# 05-ORStatusLed.net
KiCad netlist of a schematic drawn in Altium Designer
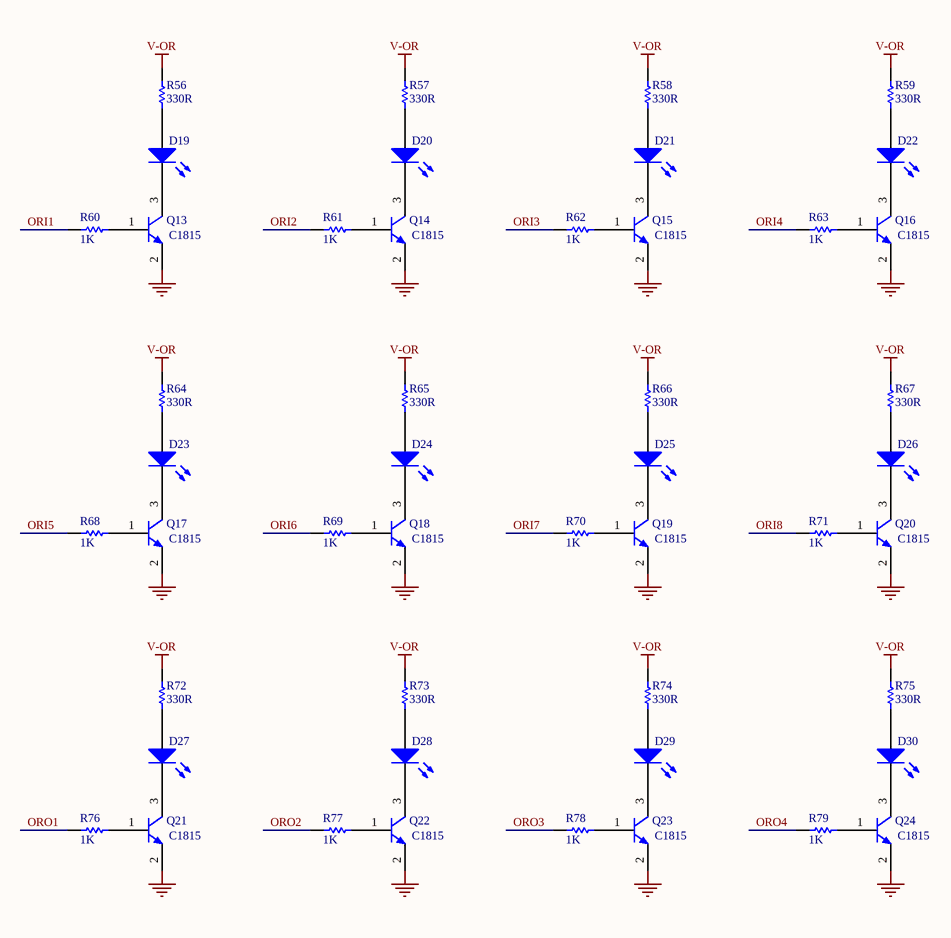
[diagram p0: 05-ORStatusLed.SchDoc]

(export (version "E")
  (design (tool "Eeschema 10.0.6"))
  (components
    (comp (ref "D19")
      (value "LED")
      (footprint "LED-3528")
      (description "Typical RED, GREEN, YELLOW, AMBER GaAs LED")
      (fields (field (name "PUBLISHER") "Altium Limited"))
      (libsource (lib "Miscellaneous Devices") (part "LED2"))
    )
    (comp (ref "D20")
      (value "LED")
      (footprint "LED-3528")
      (description "Typical RED, GREEN, YELLOW, AMBER GaAs LED")
      (fields (field (name "PUBLISHER") "Altium Limited"))
      (libsource (lib "Miscellaneous Devices") (part "LED2"))
    )
    (comp (ref "D21")
      (value "LED")
      (footprint "LED-3528")
      (description "Typical RED, GREEN, YELLOW, AMBER GaAs LED")
      (fields (field (name "PUBLISHER") "Altium Limited"))
      (libsource (lib "Miscellaneous Devices") (part "LED2"))
    )
    (comp (ref "D22")
      (value "LED")
      (footprint "LED-3528")
      (description "Typical RED, GREEN, YELLOW, AMBER GaAs LED")
      (fields (field (name "PUBLISHER") "Altium Limited"))
      (libsource (lib "Miscellaneous Devices") (part "LED2"))
    )
    (comp (ref "D23")
      (value "LED")
      (footprint "LED-3528")
      (description "Typical RED, GREEN, YELLOW, AMBER GaAs LED")
      (fields (field (name "PUBLISHER") "Altium Limited"))
      (libsource (lib "Miscellaneous Devices") (part "LED2"))
    )
    (comp (ref "D24")
      (value "LED")
      (footprint "LED-3528")
      (description "Typical RED, GREEN, YELLOW, AMBER GaAs LED")
      (fields (field (name "PUBLISHER") "Altium Limited"))
      (libsource (lib "Miscellaneous Devices") (part "LED2"))
    )
    (comp (ref "D25")
      (value "LED")
      (footprint "LED-3528")
      (description "Typical RED, GREEN, YELLOW, AMBER GaAs LED")
      (fields (field (name "PUBLISHER") "Altium Limited"))
      (libsource (lib "Miscellaneous Devices") (part "LED2"))
    )
    (comp (ref "D26")
      (value "LED")
      (footprint "LED-3528")
      (description "Typical RED, GREEN, YELLOW, AMBER GaAs LED")
      (fields (field (name "PUBLISHER") "Altium Limited"))
      (libsource (lib "Miscellaneous Devices") (part "LED2"))
    )
    (comp (ref "D27")
      (value "LED")
      (footprint "LED-3528")
      (description "Typical RED, GREEN, YELLOW, AMBER GaAs LED")
      (fields (field (name "PUBLISHER") "Altium Limited"))
      (libsource (lib "Miscellaneous Devices") (part "LED2"))
    )
    (comp (ref "D28")
      (value "LED")
      (footprint "LED-3528")
      (description "Typical RED, GREEN, YELLOW, AMBER GaAs LED")
      (fields (field (name "PUBLISHER") "Altium Limited"))
      (libsource (lib "Miscellaneous Devices") (part "LED2"))
    )
    (comp (ref "D29")
      (value "LED")
      (footprint "LED-3528")
      (description "Typical RED, GREEN, YELLOW, AMBER GaAs LED")
      (fields (field (name "PUBLISHER") "Altium Limited"))
      (libsource (lib "Miscellaneous Devices") (part "LED2"))
    )
    (comp (ref "D30")
      (value "LED")
      (footprint "LED-3528")
      (description "Typical RED, GREEN, YELLOW, AMBER GaAs LED")
      (fields (field (name "PUBLISHER") "Altium Limited"))
      (libsource (lib "Miscellaneous Devices") (part "LED2"))
    )
    (comp (ref "Q13")
      (value "C1815")
      (footprint "SOT23-321")
      (description "NPN Bipolar Transistor")
      (fields (field (name "Comment") "C1815-SMD"))
      (libsource (lib "Miscellaneous Devices") (part "NPN"))
    )
    (comp (ref "Q14")
      (value "C1815")
      (footprint "SOT23-321")
      (description "NPN Bipolar Transistor")
      (fields (field (name "Comment") "C1815-SMD"))
      (libsource (lib "Miscellaneous Devices") (part "NPN"))
    )
    (comp (ref "Q15")
      (value "C1815")
      (footprint "SOT23-321")
      (description "NPN Bipolar Transistor")
      (fields (field (name "Comment") "C1815-SMD"))
      (libsource (lib "Miscellaneous Devices") (part "NPN"))
    )
    (comp (ref "Q16")
      (value "C1815")
      (footprint "SOT23-321")
      (description "NPN Bipolar Transistor")
      (fields (field (name "Comment") "C1815-SMD"))
      (libsource (lib "Miscellaneous Devices") (part "NPN"))
    )
    (comp (ref "Q17")
      (value "C1815")
      (footprint "SOT23-321")
      (description "NPN Bipolar Transistor")
      (fields (field (name "Comment") "C1815-SMD"))
      (libsource (lib "Miscellaneous Devices") (part "NPN"))
    )
    (comp (ref "Q18")
      (value "C1815")
      (footprint "SOT23-321")
      (description "NPN Bipolar Transistor")
      (fields (field (name "Comment") "C1815-SMD"))
      (libsource (lib "Miscellaneous Devices") (part "NPN"))
    )
    (comp (ref "Q19")
      (value "C1815")
      (footprint "SOT23-321")
      (description "NPN Bipolar Transistor")
      (fields (field (name "Comment") "C1815-SMD"))
      (libsource (lib "Miscellaneous Devices") (part "NPN"))
    )
    (comp (ref "Q20")
      (value "C1815")
      (footprint "SOT23-321")
      (description "NPN Bipolar Transistor")
      (fields (field (name "Comment") "C1815-SMD"))
      (libsource (lib "Miscellaneous Devices") (part "NPN"))
    )
    (comp (ref "Q21")
      (value "C1815")
      (footprint "SOT23-321")
      (description "NPN Bipolar Transistor")
      (fields (field (name "Comment") "C1815-SMD"))
      (libsource (lib "Miscellaneous Devices") (part "NPN"))
    )
    (comp (ref "Q22")
      (value "C1815")
      (footprint "SOT23-321")
      (description "NPN Bipolar Transistor")
      (fields (field (name "Comment") "C1815-SMD"))
      (libsource (lib "Miscellaneous Devices") (part "NPN"))
    )
    (comp (ref "Q23")
      (value "C1815")
      (footprint "SOT23-321")
      (description "NPN Bipolar Transistor")
      (fields (field (name "Comment") "C1815-SMD"))
      (libsource (lib "Miscellaneous Devices") (part "NPN"))
    )
    (comp (ref "Q24")
      (value "C1815")
      (footprint "SOT23-321")
      (description "NPN Bipolar Transistor")
      (fields (field (name "Comment") "C1815-SMD"))
      (libsource (lib "Miscellaneous Devices") (part "NPN"))
    )
    (comp (ref "R56")
      (value "330R")
      (footprint "R-0805")
      (description "Resistor")
      (fields (field (name "PUBLISHER") "Altium Limited"))
      (libsource (lib "Miscellaneous Devices") (part "Res1"))
    )
    (comp (ref "R57")
      (value "330R")
      (footprint "R-0805")
      (description "Resistor")
      (fields (field (name "PUBLISHER") "Altium Limited"))
      (libsource (lib "Miscellaneous Devices") (part "Res1"))
    )
    (comp (ref "R58")
      (value "330R")
      (footprint "R-0805")
      (description "Resistor")
      (fields (field (name "PUBLISHER") "Altium Limited"))
      (libsource (lib "Miscellaneous Devices") (part "Res1"))
    )
    (comp (ref "R59")
      (value "330R")
      (footprint "R-0805")
      (description "Resistor")
      (fields (field (name "PUBLISHER") "Altium Limited"))
      (libsource (lib "Miscellaneous Devices") (part "Res1"))
    )
    (comp (ref "R60")
      (value "1K")
      (footprint "R-0805")
      (description "Resistor")
      (fields (field (name "PUBLISHER") "Altium Limited"))
      (libsource (lib "Miscellaneous Devices") (part "Res1"))
    )
    (comp (ref "R61")
      (value "1K")
      (footprint "R-0805")
      (description "Resistor")
      (fields (field (name "PUBLISHER") "Altium Limited"))
      (libsource (lib "Miscellaneous Devices") (part "Res1"))
    )
    (comp (ref "R62")
      (value "1K")
      (footprint "R-0805")
      (description "Resistor")
      (fields (field (name "PUBLISHER") "Altium Limited"))
      (libsource (lib "Miscellaneous Devices") (part "Res1"))
    )
    (comp (ref "R63")
      (value "1K")
      (footprint "R-0805")
      (description "Resistor")
      (fields (field (name "PUBLISHER") "Altium Limited"))
      (libsource (lib "Miscellaneous Devices") (part "Res1"))
    )
    (comp (ref "R64")
      (value "330R")
      (footprint "R-0805")
      (description "Resistor")
      (fields (field (name "PUBLISHER") "Altium Limited"))
      (libsource (lib "Miscellaneous Devices") (part "Res1"))
    )
    (comp (ref "R65")
      (value "330R")
      (footprint "R-0805")
      (description "Resistor")
      (fields (field (name "PUBLISHER") "Altium Limited"))
      (libsource (lib "Miscellaneous Devices") (part "Res1"))
    )
    (comp (ref "R66")
      (value "330R")
      (footprint "R-0805")
      (description "Resistor")
      (fields (field (name "PUBLISHER") "Altium Limited"))
      (libsource (lib "Miscellaneous Devices") (part "Res1"))
    )
    (comp (ref "R67")
      (value "330R")
      (footprint "R-0805")
      (description "Resistor")
      (fields (field (name "PUBLISHER") "Altium Limited"))
      (libsource (lib "Miscellaneous Devices") (part "Res1"))
    )
    (comp (ref "R68")
      (value "1K")
      (footprint "R-0805")
      (description "Resistor")
      (fields (field (name "PUBLISHER") "Altium Limited"))
      (libsource (lib "Miscellaneous Devices") (part "Res1"))
    )
    (comp (ref "R69")
      (value "1K")
      (footprint "R-0805")
      (description "Resistor")
      (fields (field (name "PUBLISHER") "Altium Limited"))
      (libsource (lib "Miscellaneous Devices") (part "Res1"))
    )
    (comp (ref "R70")
      (value "1K")
      (footprint "R-0805")
      (description "Resistor")
      (fields (field (name "PUBLISHER") "Altium Limited"))
      (libsource (lib "Miscellaneous Devices") (part "Res1"))
    )
    (comp (ref "R71")
      (value "1K")
      (footprint "R-0805")
      (description "Resistor")
      (fields (field (name "PUBLISHER") "Altium Limited"))
      (libsource (lib "Miscellaneous Devices") (part "Res1"))
    )
    (comp (ref "R72")
      (value "330R")
      (footprint "R-0805")
      (description "Resistor")
      (fields (field (name "PUBLISHER") "Altium Limited"))
      (libsource (lib "Miscellaneous Devices") (part "Res1"))
    )
    (comp (ref "R73")
      (value "330R")
      (footprint "R-0805")
      (description "Resistor")
      (fields (field (name "PUBLISHER") "Altium Limited"))
      (libsource (lib "Miscellaneous Devices") (part "Res1"))
    )
    (comp (ref "R74")
      (value "330R")
      (footprint "R-0805")
      (description "Resistor")
      (fields (field (name "PUBLISHER") "Altium Limited"))
      (libsource (lib "Miscellaneous Devices") (part "Res1"))
    )
    (comp (ref "R75")
      (value "330R")
      (footprint "R-0805")
      (description "Resistor")
      (fields (field (name "PUBLISHER") "Altium Limited"))
      (libsource (lib "Miscellaneous Devices") (part "Res1"))
    )
    (comp (ref "R76")
      (value "1K")
      (footprint "R-0805")
      (description "Resistor")
      (fields (field (name "PUBLISHER") "Altium Limited"))
      (libsource (lib "Miscellaneous Devices") (part "Res1"))
    )
    (comp (ref "R77")
      (value "1K")
      (footprint "R-0805")
      (description "Resistor")
      (fields (field (name "PUBLISHER") "Altium Limited"))
      (libsource (lib "Miscellaneous Devices") (part "Res1"))
    )
    (comp (ref "R78")
      (value "1K")
      (footprint "R-0805")
      (description "Resistor")
      (fields (field (name "PUBLISHER") "Altium Limited"))
      (libsource (lib "Miscellaneous Devices") (part "Res1"))
    )
    (comp (ref "R79")
      (value "1K")
      (footprint "R-0805")
      (description "Resistor")
      (fields (field (name "PUBLISHER") "Altium Limited"))
      (libsource (lib "Miscellaneous Devices") (part "Res1"))
    )
  )
  (nets
    (net (code "1") (name "/ORI1") (class "Default")
      (node (ref "R60") (pin "2") (pinfunction "2_2") (pintype "passive"))
    )
    (net (code "2") (name "/ORI2") (class "Default")
      (node (ref "R61") (pin "2") (pinfunction "2_2") (pintype "passive"))
    )
    (net (code "3") (name "/ORI3") (class "Default")
      (node (ref "R62") (pin "2") (pinfunction "2_2") (pintype "passive"))
    )
    (net (code "4") (name "/ORI4") (class "Default")
      (node (ref "R63") (pin "2") (pinfunction "2_2") (pintype "passive"))
    )
    (net (code "5") (name "/ORI5") (class "Default")
      (node (ref "R68") (pin "2") (pinfunction "2_2") (pintype "passive"))
    )
    (net (code "6") (name "/ORI6") (class "Default")
      (node (ref "R69") (pin "2") (pinfunction "2_2") (pintype "passive"))
    )
    (net (code "7") (name "/ORI7") (class "Default")
      (node (ref "R70") (pin "2") (pinfunction "2_2") (pintype "passive"))
    )
    (net (code "8") (name "/ORI8") (class "Default")
      (node (ref "R71") (pin "2") (pinfunction "2_2") (pintype "passive"))
    )
    (net (code "9") (name "/ORO1") (class "Default")
      (node (ref "R76") (pin "2") (pinfunction "2_2") (pintype "passive"))
    )
    (net (code "10") (name "/ORO2") (class "Default")
      (node (ref "R77") (pin "2") (pinfunction "2_2") (pintype "passive"))
    )
    (net (code "11") (name "/ORO3") (class "Default")
      (node (ref "R78") (pin "2") (pinfunction "2_2") (pintype "passive"))
    )
    (net (code "12") (name "/ORO4") (class "Default")
      (node (ref "R79") (pin "2") (pinfunction "2_2") (pintype "passive"))
    )
    (net (code "13") (name "GND") (class "Default")
      (node (ref "Q13") (pin "2") (pinfunction "E_2") (pintype "passive"))
      (node (ref "Q14") (pin "2") (pinfunction "E_2") (pintype "passive"))
      (node (ref "Q15") (pin "2") (pinfunction "E_2") (pintype "passive"))
      (node (ref "Q16") (pin "2") (pinfunction "E_2") (pintype "passive"))
      (node (ref "Q17") (pin "2") (pinfunction "E_2") (pintype "passive"))
      (node (ref "Q18") (pin "2") (pinfunction "E_2") (pintype "passive"))
      (node (ref "Q19") (pin "2") (pinfunction "E_2") (pintype "passive"))
      (node (ref "Q20") (pin "2") (pinfunction "E_2") (pintype "passive"))
      (node (ref "Q21") (pin "2") (pinfunction "E_2") (pintype "passive"))
      (node (ref "Q22") (pin "2") (pinfunction "E_2") (pintype "passive"))
      (node (ref "Q23") (pin "2") (pinfunction "E_2") (pintype "passive"))
      (node (ref "Q24") (pin "2") (pinfunction "E_2") (pintype "passive"))
    )
    (net (code "14") (name "Net-(D19-A)") (class "Default")
      (node (ref "D19") (pin "1") (pinfunction "A_1") (pintype "passive"))
      (node (ref "R56") (pin "1") (pinfunction "1_1") (pintype "passive"))
    )
    (net (code "15") (name "Net-(D19-K)") (class "Default")
      (node (ref "D19") (pin "2") (pinfunction "K_2") (pintype "passive"))
      (node (ref "Q13") (pin "3") (pinfunction "C_3") (pintype "passive"))
    )
    (net (code "16") (name "Net-(D20-A)") (class "Default")
      (node (ref "D20") (pin "1") (pinfunction "A_1") (pintype "passive"))
      (node (ref "R57") (pin "1") (pinfunction "1_1") (pintype "passive"))
    )
    (net (code "17") (name "Net-(D20-K)") (class "Default")
      (node (ref "D20") (pin "2") (pinfunction "K_2") (pintype "passive"))
      (node (ref "Q14") (pin "3") (pinfunction "C_3") (pintype "passive"))
    )
    (net (code "18") (name "Net-(D21-A)") (class "Default")
      (node (ref "D21") (pin "1") (pinfunction "A_1") (pintype "passive"))
      (node (ref "R58") (pin "1") (pinfunction "1_1") (pintype "passive"))
    )
    (net (code "19") (name "Net-(D21-K)") (class "Default")
      (node (ref "D21") (pin "2") (pinfunction "K_2") (pintype "passive"))
      (node (ref "Q15") (pin "3") (pinfunction "C_3") (pintype "passive"))
    )
    (net (code "20") (name "Net-(D22-A)") (class "Default")
      (node (ref "D22") (pin "1") (pinfunction "A_1") (pintype "passive"))
      (node (ref "R59") (pin "1") (pinfunction "1_1") (pintype "passive"))
    )
    (net (code "21") (name "Net-(D22-K)") (class "Default")
      (node (ref "D22") (pin "2") (pinfunction "K_2") (pintype "passive"))
      (node (ref "Q16") (pin "3") (pinfunction "C_3") (pintype "passive"))
    )
    (net (code "22") (name "Net-(D23-A)") (class "Default")
      (node (ref "D23") (pin "1") (pinfunction "A_1") (pintype "passive"))
      (node (ref "R64") (pin "1") (pinfunction "1_1") (pintype "passive"))
    )
    (net (code "23") (name "Net-(D23-K)") (class "Default")
      (node (ref "D23") (pin "2") (pinfunction "K_2") (pintype "passive"))
      (node (ref "Q17") (pin "3") (pinfunction "C_3") (pintype "passive"))
    )
    (net (code "24") (name "Net-(D24-A)") (class "Default")
      (node (ref "D24") (pin "1") (pinfunction "A_1") (pintype "passive"))
      (node (ref "R65") (pin "1") (pinfunction "1_1") (pintype "passive"))
    )
    (net (code "25") (name "Net-(D24-K)") (class "Default")
      (node (ref "D24") (pin "2") (pinfunction "K_2") (pintype "passive"))
      (node (ref "Q18") (pin "3") (pinfunction "C_3") (pintype "passive"))
    )
    (net (code "26") (name "Net-(D25-A)") (class "Default")
      (node (ref "D25") (pin "1") (pinfunction "A_1") (pintype "passive"))
      (node (ref "R66") (pin "1") (pinfunction "1_1") (pintype "passive"))
    )
    (net (code "27") (name "Net-(D25-K)") (class "Default")
      (node (ref "D25") (pin "2") (pinfunction "K_2") (pintype "passive"))
      (node (ref "Q19") (pin "3") (pinfunction "C_3") (pintype "passive"))
    )
    (net (code "28") (name "Net-(D26-A)") (class "Default")
      (node (ref "D26") (pin "1") (pinfunction "A_1") (pintype "passive"))
      (node (ref "R67") (pin "1") (pinfunction "1_1") (pintype "passive"))
    )
    (net (code "29") (name "Net-(D26-K)") (class "Default")
      (node (ref "D26") (pin "2") (pinfunction "K_2") (pintype "passive"))
      (node (ref "Q20") (pin "3") (pinfunction "C_3") (pintype "passive"))
    )
    (net (code "30") (name "Net-(D27-A)") (class "Default")
      (node (ref "D27") (pin "1") (pinfunction "A_1") (pintype "passive"))
      (node (ref "R72") (pin "1") (pinfunction "1_1") (pintype "passive"))
    )
    (net (code "31") (name "Net-(D27-K)") (class "Default")
      (node (ref "D27") (pin "2") (pinfunction "K_2") (pintype "passive"))
      (node (ref "Q21") (pin "3") (pinfunction "C_3") (pintype "passive"))
    )
    (net (code "32") (name "Net-(D28-A)") (class "Default")
      (node (ref "D28") (pin "1") (pinfunction "A_1") (pintype "passive"))
      (node (ref "R73") (pin "1") (pinfunction "1_1") (pintype "passive"))
    )
    (net (code "33") (name "Net-(D28-K)") (class "Default")
      (node (ref "D28") (pin "2") (pinfunction "K_2") (pintype "passive"))
      (node (ref "Q22") (pin "3") (pinfunction "C_3") (pintype "passive"))
    )
    (net (code "34") (name "Net-(D29-A)") (class "Default")
      (node (ref "D29") (pin "1") (pinfunction "A_1") (pintype "passive"))
      (node (ref "R74") (pin "1") (pinfunction "1_1") (pintype "passive"))
    )
    (net (code "35") (name "Net-(D29-K)") (class "Default")
      (node (ref "D29") (pin "2") (pinfunction "K_2") (pintype "passive"))
      (node (ref "Q23") (pin "3") (pinfunction "C_3") (pintype "passive"))
    )
    (net (code "36") (name "Net-(D30-A)") (class "Default")
      (node (ref "D30") (pin "1") (pinfunction "A_1") (pintype "passive"))
      (node (ref "R75") (pin "1") (pinfunction "1_1") (pintype "passive"))
    )
    (net (code "37") (name "Net-(D30-K)") (class "Default")
      (node (ref "D30") (pin "2") (pinfunction "K_2") (pintype "passive"))
      (node (ref "Q24") (pin "3") (pinfunction "C_3") (pintype "passive"))
    )
    (net (code "38") (name "Net-(Q13-B)") (class "Default")
      (node (ref "Q13") (pin "1") (pinfunction "B_1") (pintype "passive"))
      (node (ref "R60") (pin "1") (pinfunction "1_1") (pintype "passive"))
    )
    (net (code "39") (name "Net-(Q14-B)") (class "Default")
      (node (ref "Q14") (pin "1") (pinfunction "B_1") (pintype "passive"))
      (node (ref "R61") (pin "1") (pinfunction "1_1") (pintype "passive"))
    )
    (net (code "40") (name "Net-(Q15-B)") (class "Default")
      (node (ref "Q15") (pin "1") (pinfunction "B_1") (pintype "passive"))
      (node (ref "R62") (pin "1") (pinfunction "1_1") (pintype "passive"))
    )
    (net (code "41") (name "Net-(Q16-B)") (class "Default")
      (node (ref "Q16") (pin "1") (pinfunction "B_1") (pintype "passive"))
      (node (ref "R63") (pin "1") (pinfunction "1_1") (pintype "passive"))
    )
    (net (code "42") (name "Net-(Q17-B)") (class "Default")
      (node (ref "Q17") (pin "1") (pinfunction "B_1") (pintype "passive"))
      (node (ref "R68") (pin "1") (pinfunction "1_1") (pintype "passive"))
    )
    (net (code "43") (name "Net-(Q18-B)") (class "Default")
      (node (ref "Q18") (pin "1") (pinfunction "B_1") (pintype "passive"))
      (node (ref "R69") (pin "1") (pinfunction "1_1") (pintype "passive"))
    )
    (net (code "44") (name "Net-(Q19-B)") (class "Default")
      (node (ref "Q19") (pin "1") (pinfunction "B_1") (pintype "passive"))
      (node (ref "R70") (pin "1") (pinfunction "1_1") (pintype "passive"))
    )
    (net (code "45") (name "Net-(Q20-B)") (class "Default")
      (node (ref "Q20") (pin "1") (pinfunction "B_1") (pintype "passive"))
      (node (ref "R71") (pin "1") (pinfunction "1_1") (pintype "passive"))
    )
    (net (code "46") (name "Net-(Q21-B)") (class "Default")
      (node (ref "Q21") (pin "1") (pinfunction "B_1") (pintype "passive"))
      (node (ref "R76") (pin "1") (pinfunction "1_1") (pintype "passive"))
    )
    (net (code "47") (name "Net-(Q22-B)") (class "Default")
      (node (ref "Q22") (pin "1") (pinfunction "B_1") (pintype "passive"))
      (node (ref "R77") (pin "1") (pinfunction "1_1") (pintype "passive"))
    )
    (net (code "48") (name "Net-(Q23-B)") (class "Default")
      (node (ref "Q23") (pin "1") (pinfunction "B_1") (pintype "passive"))
      (node (ref "R78") (pin "1") (pinfunction "1_1") (pintype "passive"))
    )
    (net (code "49") (name "Net-(Q24-B)") (class "Default")
      (node (ref "Q24") (pin "1") (pinfunction "B_1") (pintype "passive"))
      (node (ref "R79") (pin "1") (pinfunction "1_1") (pintype "passive"))
    )
    (net (code "50") (name "V-OR") (class "Default")
      (node (ref "R56") (pin "2") (pinfunction "2_2") (pintype "passive"))
      (node (ref "R57") (pin "2") (pinfunction "2_2") (pintype "passive"))
      (node (ref "R58") (pin "2") (pinfunction "2_2") (pintype "passive"))
      (node (ref "R59") (pin "2") (pinfunction "2_2") (pintype "passive"))
      (node (ref "R64") (pin "2") (pinfunction "2_2") (pintype "passive"))
      (node (ref "R65") (pin "2") (pinfunction "2_2") (pintype "passive"))
      (node (ref "R66") (pin "2") (pinfunction "2_2") (pintype "passive"))
      (node (ref "R67") (pin "2") (pinfunction "2_2") (pintype "passive"))
      (node (ref "R72") (pin "2") (pinfunction "2_2") (pintype "passive"))
      (node (ref "R73") (pin "2") (pinfunction "2_2") (pintype "passive"))
      (node (ref "R74") (pin "2") (pinfunction "2_2") (pintype "passive"))
      (node (ref "R75") (pin "2") (pinfunction "2_2") (pintype "passive"))
    )
  )
)
